# TMR1_v2.net
KiCad netlist of a schematic drawn in EAGLE
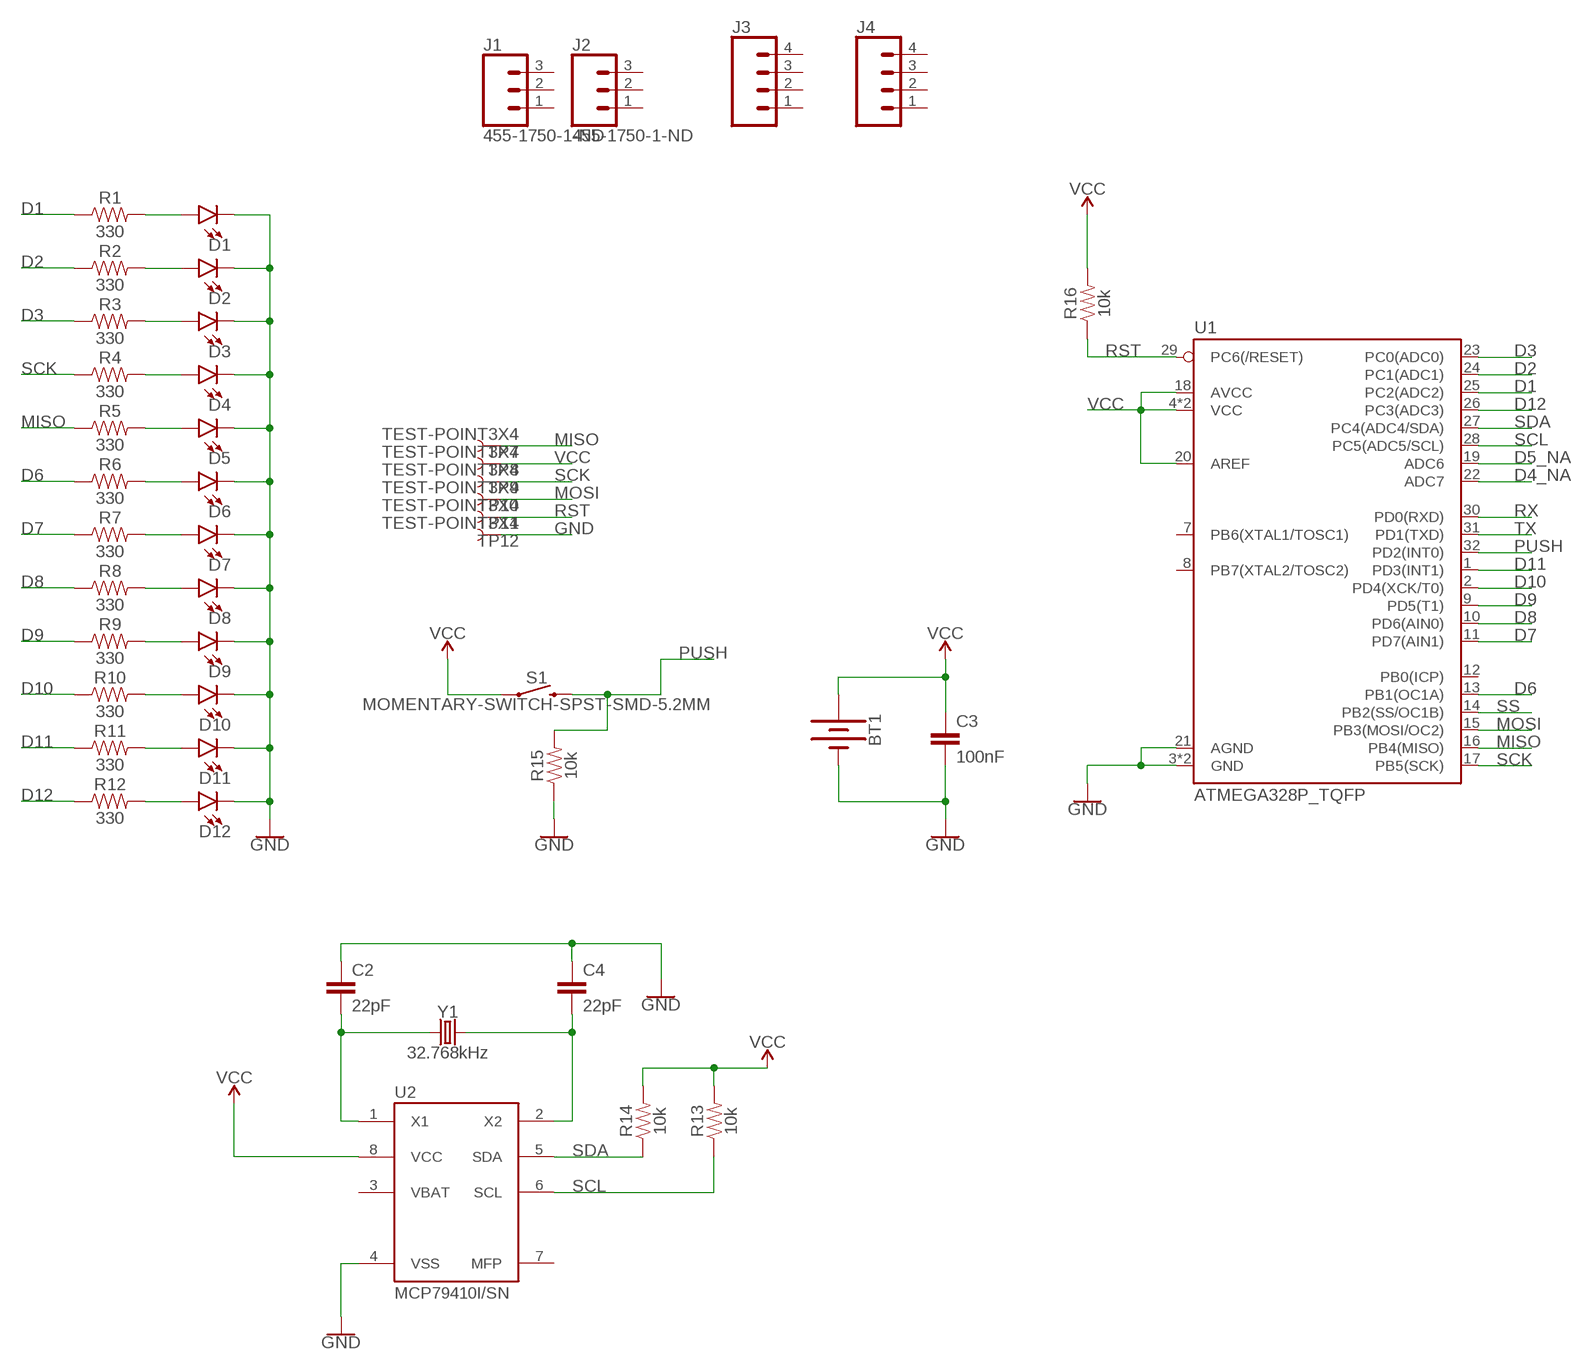
[diagram p0: schematic, sheet 1]

(export (version "E")
  (design (tool "Eeschema 10.0.6"))
  (components
    (comp (ref "BT1")
      (value "BATTERY-20MM_SMD_4LEGS")
      (footprint "eagle-import:BATTCON_20MM_4LEGS")
      (libsource (lib "eagle-import") (part "BATTERY-20MM_SMD_4LEGS"))
    )
    (comp (ref "C2")
      (value "22pF")
      (footprint "eagle-import:0603")
      (libsource (lib "eagle-import") (part "22PF-0603-50V-5%"))
    )
    (comp (ref "C3")
      (value "100nF")
      (footprint "eagle-import:0603")
      (libsource (lib "eagle-import") (part "22PF-0603-50V-5%"))
    )
    (comp (ref "C4")
      (value "22pF")
      (footprint "eagle-import:0603")
      (libsource (lib "eagle-import") (part "22PF-0603-50V-5%"))
    )
    (comp (ref "D1")
      (value "LED0603")
      (footprint "eagle-import:LED-0603")
      (libsource (lib "eagle-import") (part "LED0603"))
    )
    (comp (ref "D2")
      (value "LED0603")
      (footprint "eagle-import:LED-0603")
      (libsource (lib "eagle-import") (part "LED0603"))
    )
    (comp (ref "D3")
      (value "LED0603")
      (footprint "eagle-import:LED-0603")
      (libsource (lib "eagle-import") (part "LED0603"))
    )
    (comp (ref "D4")
      (value "LED0603")
      (footprint "eagle-import:LED-0603")
      (libsource (lib "eagle-import") (part "LED0603"))
    )
    (comp (ref "D5")
      (value "LED0603")
      (footprint "eagle-import:LED-0603")
      (libsource (lib "eagle-import") (part "LED0603"))
    )
    (comp (ref "D6")
      (value "LED0603")
      (footprint "eagle-import:LED-0603")
      (libsource (lib "eagle-import") (part "LED0603"))
    )
    (comp (ref "D7")
      (value "LED0603")
      (footprint "eagle-import:LED-0603")
      (libsource (lib "eagle-import") (part "LED0603"))
    )
    (comp (ref "D8")
      (value "LED0603")
      (footprint "eagle-import:LED-0603")
      (libsource (lib "eagle-import") (part "LED0603"))
    )
    (comp (ref "D9")
      (value "LED0603")
      (footprint "eagle-import:LED-0603")
      (libsource (lib "eagle-import") (part "LED0603"))
    )
    (comp (ref "D10")
      (value "LED0603")
      (footprint "eagle-import:LED-0603")
      (libsource (lib "eagle-import") (part "LED0603"))
    )
    (comp (ref "D11")
      (value "LED0603")
      (footprint "eagle-import:LED-0603")
      (libsource (lib "eagle-import") (part "LED0603"))
    )
    (comp (ref "D12")
      (value "LED0603")
      (footprint "eagle-import:LED-0603")
      (libsource (lib "eagle-import") (part "LED0603"))
    )
    (comp (ref "J1")
      (value "455-1750-1-ND")
      (footprint "eagle-import:1X03")
      (libsource (lib "eagle-import") (part "CONN_03"))
    )
    (comp (ref "J2")
      (value "455-1750-1-ND")
      (footprint "eagle-import:1X03")
      (libsource (lib "eagle-import") (part "CONN_03"))
    )
    (comp (ref "J3")
      (value "CONN_04")
      (footprint "eagle-import:1X04")
      (libsource (lib "eagle-import") (part "CONN_04"))
    )
    (comp (ref "J4")
      (value "CONN_04")
      (footprint "eagle-import:1X04")
      (libsource (lib "eagle-import") (part "CONN_04"))
    )
    (comp (ref "R1")
      (value "330")
      (footprint "eagle-import:0603")
      (libsource (lib "eagle-import") (part "330OHM-0603-1/10W-1%"))
    )
    (comp (ref "R2")
      (value "330")
      (footprint "eagle-import:0603")
      (libsource (lib "eagle-import") (part "330OHM-0603-1/10W-1%"))
    )
    (comp (ref "R3")
      (value "330")
      (footprint "eagle-import:0603")
      (libsource (lib "eagle-import") (part "330OHM-0603-1/10W-1%"))
    )
    (comp (ref "R4")
      (value "330")
      (footprint "eagle-import:0603")
      (libsource (lib "eagle-import") (part "330OHM-0603-1/10W-1%"))
    )
    (comp (ref "R5")
      (value "330")
      (footprint "eagle-import:0603")
      (libsource (lib "eagle-import") (part "330OHM-0603-1/10W-1%"))
    )
    (comp (ref "R6")
      (value "330")
      (footprint "eagle-import:0603")
      (libsource (lib "eagle-import") (part "330OHM-0603-1/10W-1%"))
    )
    (comp (ref "R7")
      (value "330")
      (footprint "eagle-import:0603")
      (libsource (lib "eagle-import") (part "330OHM-0603-1/10W-1%"))
    )
    (comp (ref "R8")
      (value "330")
      (footprint "eagle-import:0603")
      (libsource (lib "eagle-import") (part "330OHM-0603-1/10W-1%"))
    )
    (comp (ref "R9")
      (value "330")
      (footprint "eagle-import:0603")
      (libsource (lib "eagle-import") (part "330OHM-0603-1/10W-1%"))
    )
    (comp (ref "R10")
      (value "330")
      (footprint "eagle-import:0603")
      (libsource (lib "eagle-import") (part "330OHM-0603-1/10W-1%"))
    )
    (comp (ref "R11")
      (value "330")
      (footprint "eagle-import:0603")
      (libsource (lib "eagle-import") (part "330OHM-0603-1/10W-1%"))
    )
    (comp (ref "R12")
      (value "330")
      (footprint "eagle-import:0603")
      (libsource (lib "eagle-import") (part "330OHM-0603-1/10W-1%"))
    )
    (comp (ref "R13")
      (value "10k")
      (footprint "eagle-import:0603")
      (libsource (lib "eagle-import") (part "10KOHM-0603-1/10W-1%"))
    )
    (comp (ref "R14")
      (value "10k")
      (footprint "eagle-import:0603")
      (libsource (lib "eagle-import") (part "10KOHM-0603-1/10W-1%"))
    )
    (comp (ref "R15")
      (value "10k")
      (footprint "eagle-import:0603")
      (libsource (lib "eagle-import") (part "10KOHM-0603-1/10W-1%"))
    )
    (comp (ref "R16")
      (value "10k")
      (footprint "eagle-import:0603")
      (libsource (lib "eagle-import") (part "10KOHM-0603-1/10W-1%"))
    )
    (comp (ref "S1")
      (value "MOMENTARY-SWITCH-SPST-SMD-5.2MM")
      (footprint "eagle-import:TACTILE_SWITCH_SMD_5.2MM")
      (libsource (lib "eagle-import") (part "MOMENTARY-SWITCH-SPST-SMD-5.2MM"))
    )
    (comp (ref "TP7")
      (value "TEST-POINT3X4")
      (footprint "eagle-import:PAD.03X.04")
      (libsource (lib "eagle-import") (part "TEST-POINT3X4"))
    )
    (comp (ref "TP8")
      (value "TEST-POINT3X4")
      (footprint "eagle-import:PAD.03X.04")
      (libsource (lib "eagle-import") (part "TEST-POINT3X4"))
    )
    (comp (ref "TP9")
      (value "TEST-POINT3X4")
      (footprint "eagle-import:PAD.03X.04")
      (libsource (lib "eagle-import") (part "TEST-POINT3X4"))
    )
    (comp (ref "TP10")
      (value "TEST-POINT3X4")
      (footprint "eagle-import:PAD.03X.04")
      (libsource (lib "eagle-import") (part "TEST-POINT3X4"))
    )
    (comp (ref "TP11")
      (value "TEST-POINT3X4")
      (footprint "eagle-import:PAD.03X.04")
      (libsource (lib "eagle-import") (part "TEST-POINT3X4"))
    )
    (comp (ref "TP12")
      (value "TEST-POINT3X4")
      (footprint "eagle-import:PAD.03X.04")
      (libsource (lib "eagle-import") (part "TEST-POINT3X4"))
    )
    (comp (ref "U1")
      (value "ATMEGA328P_TQFP")
      (footprint "eagle-import:TQFP32-08")
      (libsource (lib "eagle-import") (part "ATMEGA328P_TQFP"))
    )
    (comp (ref "U2")
      (value "MCP79410I/SN")
      (footprint "eagle-import:SO8")
      (libsource (lib "eagle-import") (part "MCP7941?/SN0I"))
    )
    (comp (ref "Y1")
      (value "32.768kHz")
      (footprint "eagle-import:CRYSTAL-SMD-MC-146")
      (libsource (lib "eagle-import") (part "CRYSTAL-32.768KHZSMD-MC146"))
    )
  )
  (nets
    (net (code "1") (name "/D1") (class "Default")
      (node (ref "R1") (pin "1") (pinfunction "1_1") (pintype "passive"))
      (node (ref "U1") (pin "25") (pinfunction "PC2(ADC2)_25") (pintype "bidirectional"))
    )
    (net (code "2") (name "/D2") (class "Default")
      (node (ref "R2") (pin "1") (pinfunction "1_1") (pintype "passive"))
      (node (ref "U1") (pin "24") (pinfunction "PC1(ADC1)_24") (pintype "bidirectional"))
    )
    (net (code "3") (name "/D3") (class "Default")
      (node (ref "R3") (pin "1") (pinfunction "1_1") (pintype "passive"))
      (node (ref "U1") (pin "23") (pinfunction "PC0(ADC0)_23") (pintype "bidirectional"))
    )
    (net (code "4") (name "/D4_NA") (class "Default")
      (node (ref "U1") (pin "22") (pinfunction "ADC7_22") (pintype "bidirectional"))
    )
    (net (code "5") (name "/D5_NA") (class "Default")
      (node (ref "U1") (pin "19") (pinfunction "ADC6_19") (pintype "bidirectional"))
    )
    (net (code "6") (name "/D6") (class "Default")
      (node (ref "R6") (pin "1") (pinfunction "1_1") (pintype "passive"))
      (node (ref "U1") (pin "13") (pinfunction "PB1(OC1A)_13") (pintype "bidirectional"))
    )
    (net (code "7") (name "/D7") (class "Default")
      (node (ref "R7") (pin "1") (pinfunction "1_1") (pintype "passive"))
      (node (ref "U1") (pin "11") (pinfunction "PD7(AIN1)_11") (pintype "bidirectional"))
    )
    (net (code "8") (name "/D8") (class "Default")
      (node (ref "R8") (pin "1") (pinfunction "1_1") (pintype "passive"))
      (node (ref "U1") (pin "10") (pinfunction "PD6(AIN0)_10") (pintype "bidirectional"))
    )
    (net (code "9") (name "/D9") (class "Default")
      (node (ref "R9") (pin "1") (pinfunction "1_1") (pintype "passive"))
      (node (ref "U1") (pin "9") (pinfunction "PD5(T1)_9") (pintype "bidirectional"))
    )
    (net (code "10") (name "/D10") (class "Default")
      (node (ref "R10") (pin "1") (pinfunction "1_1") (pintype "passive"))
      (node (ref "U1") (pin "2") (pinfunction "PD4(XCK/T0)_2") (pintype "bidirectional"))
    )
    (net (code "11") (name "/D11") (class "Default")
      (node (ref "R11") (pin "1") (pinfunction "1_1") (pintype "passive"))
      (node (ref "U1") (pin "1") (pinfunction "PD3(INT1)_1") (pintype "bidirectional"))
    )
    (net (code "12") (name "/D12") (class "Default")
      (node (ref "R12") (pin "1") (pinfunction "1_1") (pintype "passive"))
      (node (ref "U1") (pin "26") (pinfunction "PC3(ADC3)_26") (pintype "bidirectional"))
    )
    (net (code "13") (name "/MISO") (class "Default")
      (node (ref "R5") (pin "1") (pinfunction "1_1") (pintype "passive"))
      (node (ref "TP7") (pin "P$1") (pinfunction "1_P$1") (pintype "bidirectional"))
      (node (ref "U1") (pin "16") (pinfunction "PB4(MISO)_16") (pintype "bidirectional"))
    )
    (net (code "14") (name "/MOSI") (class "Default")
      (node (ref "TP10") (pin "P$1") (pinfunction "1_P$1") (pintype "bidirectional"))
      (node (ref "U1") (pin "15") (pinfunction "PB3(MOSI/OC2)_15") (pintype "bidirectional"))
    )
    (net (code "15") (name "/PUSH") (class "Default")
      (node (ref "R15") (pin "2") (pinfunction "2_2") (pintype "passive"))
      (node (ref "S1") (pin "3") (pinfunction "2_3") (pintype "passive"))
      (node (ref "U1") (pin "32") (pinfunction "PD2(INT0)_32") (pintype "bidirectional"))
    )
    (net (code "16") (name "/RST") (class "Default")
      (node (ref "R16") (pin "1") (pinfunction "1_1") (pintype "passive"))
      (node (ref "TP11") (pin "P$1") (pinfunction "1_P$1") (pintype "bidirectional"))
      (node (ref "U1") (pin "29") (pinfunction "PC6(/RESET)_29") (pintype "bidirectional"))
    )
    (net (code "17") (name "/RX") (class "Default")
      (node (ref "U1") (pin "30") (pinfunction "PD0(RXD)_30") (pintype "bidirectional"))
    )
    (net (code "18") (name "/SCK") (class "Default")
      (node (ref "R4") (pin "1") (pinfunction "1_1") (pintype "passive"))
      (node (ref "TP9") (pin "P$1") (pinfunction "1_P$1") (pintype "bidirectional"))
      (node (ref "U1") (pin "17") (pinfunction "PB5(SCK)_17") (pintype "bidirectional"))
    )
    (net (code "19") (name "/SCL") (class "Default")
      (node (ref "R13") (pin "1") (pinfunction "1_1") (pintype "passive"))
      (node (ref "U1") (pin "28") (pinfunction "PC5(ADC5/SCL)_28") (pintype "bidirectional"))
      (node (ref "U2") (pin "6") (pinfunction "SCL_6") (pintype "input"))
    )
    (net (code "20") (name "/SDA") (class "Default")
      (node (ref "R14") (pin "1") (pinfunction "1_1") (pintype "passive"))
      (node (ref "U1") (pin "27") (pinfunction "PC4(ADC4/SDA)_27") (pintype "bidirectional"))
      (node (ref "U2") (pin "5") (pinfunction "SDA_5") (pintype "open_collector"))
    )
    (net (code "21") (name "/SS") (class "Default")
      (node (ref "U1") (pin "14") (pinfunction "PB2(SS/OC1B)_14") (pintype "bidirectional"))
    )
    (net (code "22") (name "/TX") (class "Default")
      (node (ref "U1") (pin "31") (pinfunction "PD1(TXD)_31") (pintype "bidirectional"))
    )
    (net (code "23") (name "/VBAT") (class "Default")
      (node (ref "U2") (pin "3") (pinfunction "VBAT_3") (pintype "power_in"))
    )
    (net (code "24") (name "GND") (class "Default")
      (node (ref "BT1") (pin "NEGATIVE") (pinfunction "-_NEGATIVE") (pintype "power_in"))
      (node (ref "C2") (pin "1") (pinfunction "1_1") (pintype "passive"))
      (node (ref "C3") (pin "2") (pinfunction "2_2") (pintype "passive"))
      (node (ref "C4") (pin "1") (pinfunction "1_1") (pintype "passive"))
      (node (ref "D1") (pin "C") (pinfunction "C_C") (pintype "passive"))
      (node (ref "D10") (pin "C") (pinfunction "C_C") (pintype "passive"))
      (node (ref "D11") (pin "C") (pinfunction "C_C") (pintype "passive"))
      (node (ref "D12") (pin "C") (pinfunction "C_C") (pintype "passive"))
      (node (ref "D2") (pin "C") (pinfunction "C_C") (pintype "passive"))
      (node (ref "D3") (pin "C") (pinfunction "C_C") (pintype "passive"))
      (node (ref "D4") (pin "C") (pinfunction "C_C") (pintype "passive"))
      (node (ref "D5") (pin "C") (pinfunction "C_C") (pintype "passive"))
      (node (ref "D6") (pin "C") (pinfunction "C_C") (pintype "passive"))
      (node (ref "D7") (pin "C") (pinfunction "C_C") (pintype "passive"))
      (node (ref "D8") (pin "C") (pinfunction "C_C") (pintype "passive"))
      (node (ref "D9") (pin "C") (pinfunction "C_C") (pintype "passive"))
      (node (ref "R15") (pin "1") (pinfunction "1_1") (pintype "passive"))
      (node (ref "TP12") (pin "P$1") (pinfunction "1_P$1") (pintype "bidirectional"))
      (node (ref "U1") (pin "21") (pinfunction "AGND_21") (pintype "bidirectional"))
      (node (ref "U1") (pin "3") (pinfunction "GND_3") (pintype "bidirectional"))
      (node (ref "U1") (pin "5") (pinfunction "GND_5") (pintype "bidirectional"))
      (node (ref "U2") (pin "4") (pinfunction "VSS_4") (pintype "power_in"))
    )
    (net (code "25") (name "Net-(D1-PadA)") (class "Default")
      (node (ref "D1") (pin "A") (pinfunction "A_A") (pintype "passive"))
      (node (ref "R1") (pin "2") (pinfunction "2_2") (pintype "passive"))
    )
    (net (code "26") (name "Net-(D2-PadA)") (class "Default")
      (node (ref "D2") (pin "A") (pinfunction "A_A") (pintype "passive"))
      (node (ref "R2") (pin "2") (pinfunction "2_2") (pintype "passive"))
    )
    (net (code "27") (name "Net-(D3-PadA)") (class "Default")
      (node (ref "D3") (pin "A") (pinfunction "A_A") (pintype "passive"))
      (node (ref "R3") (pin "2") (pinfunction "2_2") (pintype "passive"))
    )
    (net (code "28") (name "Net-(D4-PadA)") (class "Default")
      (node (ref "D4") (pin "A") (pinfunction "A_A") (pintype "passive"))
      (node (ref "R4") (pin "2") (pinfunction "2_2") (pintype "passive"))
    )
    (net (code "29") (name "Net-(D5-PadA)") (class "Default")
      (node (ref "D5") (pin "A") (pinfunction "A_A") (pintype "passive"))
      (node (ref "R5") (pin "2") (pinfunction "2_2") (pintype "passive"))
    )
    (net (code "30") (name "Net-(D6-PadA)") (class "Default")
      (node (ref "D6") (pin "A") (pinfunction "A_A") (pintype "passive"))
      (node (ref "R6") (pin "2") (pinfunction "2_2") (pintype "passive"))
    )
    (net (code "31") (name "Net-(D7-PadA)") (class "Default")
      (node (ref "D7") (pin "A") (pinfunction "A_A") (pintype "passive"))
      (node (ref "R7") (pin "2") (pinfunction "2_2") (pintype "passive"))
    )
    (net (code "32") (name "Net-(D8-PadA)") (class "Default")
      (node (ref "D8") (pin "A") (pinfunction "A_A") (pintype "passive"))
      (node (ref "R8") (pin "2") (pinfunction "2_2") (pintype "passive"))
    )
    (net (code "33") (name "Net-(D9-PadA)") (class "Default")
      (node (ref "D9") (pin "A") (pinfunction "A_A") (pintype "passive"))
      (node (ref "R9") (pin "2") (pinfunction "2_2") (pintype "passive"))
    )
    (net (code "34") (name "Net-(D10-PadA)") (class "Default")
      (node (ref "D10") (pin "A") (pinfunction "A_A") (pintype "passive"))
      (node (ref "R10") (pin "2") (pinfunction "2_2") (pintype "passive"))
    )
    (net (code "35") (name "Net-(D11-PadA)") (class "Default")
      (node (ref "D11") (pin "A") (pinfunction "A_A") (pintype "passive"))
      (node (ref "R11") (pin "2") (pinfunction "2_2") (pintype "passive"))
    )
    (net (code "36") (name "Net-(D12-PadA)") (class "Default")
      (node (ref "D12") (pin "A") (pinfunction "A_A") (pintype "passive"))
      (node (ref "R12") (pin "2") (pinfunction "2_2") (pintype "passive"))
    )
    (net (code "37") (name "Net-(U2-X1)") (class "Default")
      (node (ref "C2") (pin "2") (pinfunction "2_2") (pintype "passive"))
      (node (ref "U2") (pin "1") (pinfunction "X1_1") (pintype "input"))
      (node (ref "Y1") (pin "P$2") (pinfunction "1_P$2") (pintype "passive"))
    )
    (net (code "38") (name "Net-(U2-X2)") (class "Default")
      (node (ref "C4") (pin "2") (pinfunction "2_2") (pintype "passive"))
      (node (ref "U2") (pin "2") (pinfunction "X2_2") (pintype "output"))
      (node (ref "Y1") (pin "P$1") (pinfunction "2_P$1") (pintype "passive"))
    )
    (net (code "39") (name "VCC") (class "Default")
      (node (ref "BT1") (pin "POSITIVE@1") (pinfunction "+_POSITIVE@1") (pintype "power_in"))
      (node (ref "BT1") (pin "POSITIVE@2") (pinfunction "+_POSITIVE@2") (pintype "power_in"))
      (node (ref "BT1") (pin "POSITIVE@3") (pinfunction "+_POSITIVE@3") (pintype "power_in"))
      (node (ref "BT1") (pin "POSITIVE@4") (pinfunction "+_POSITIVE@4") (pintype "power_in"))
      (node (ref "C3") (pin "1") (pinfunction "1_1") (pintype "passive"))
      (node (ref "R13") (pin "2") (pinfunction "2_2") (pintype "passive"))
      (node (ref "R14") (pin "2") (pinfunction "2_2") (pintype "passive"))
      (node (ref "R16") (pin "2") (pinfunction "2_2") (pintype "passive"))
      (node (ref "S1") (pin "1") (pinfunction "1_1") (pintype "passive"))
      (node (ref "TP8") (pin "P$1") (pinfunction "1_P$1") (pintype "bidirectional"))
      (node (ref "U1") (pin "18") (pinfunction "AVCC_18") (pintype "bidirectional"))
      (node (ref "U1") (pin "20") (pinfunction "AREF_20") (pintype "bidirectional"))
      (node (ref "U1") (pin "4") (pinfunction "VCC_4") (pintype "bidirectional"))
      (node (ref "U1") (pin "6") (pinfunction "VCC_6") (pintype "bidirectional"))
      (node (ref "U2") (pin "8") (pinfunction "VCC_8") (pintype "power_in"))
    )
    (net (code "40") (name "unconnected-(J1-Pad1)") (class "Default")
      (node (ref "J1") (pin "1") (pinfunction "1_1") (pintype "passive"))
    )
    (net (code "41") (name "unconnected-(J1-Pad2)") (class "Default")
      (node (ref "J1") (pin "2") (pinfunction "2_2") (pintype "passive"))
    )
    (net (code "42") (name "unconnected-(J1-Pad3)") (class "Default")
      (node (ref "J1") (pin "3") (pinfunction "3_3") (pintype "passive"))
    )
    (net (code "43") (name "unconnected-(J2-Pad1)") (class "Default")
      (node (ref "J2") (pin "1") (pinfunction "1_1") (pintype "passive"))
    )
    (net (code "44") (name "unconnected-(J2-Pad2)") (class "Default")
      (node (ref "J2") (pin "2") (pinfunction "2_2") (pintype "passive"))
    )
    (net (code "45") (name "unconnected-(J2-Pad3)") (class "Default")
      (node (ref "J2") (pin "3") (pinfunction "3_3") (pintype "passive"))
    )
    (net (code "46") (name "unconnected-(J3-Pad1)") (class "Default")
      (node (ref "J3") (pin "1") (pinfunction "1_1") (pintype "passive"))
    )
    (net (code "47") (name "unconnected-(J3-Pad2)") (class "Default")
      (node (ref "J3") (pin "2") (pinfunction "2_2") (pintype "passive"))
    )
    (net (code "48") (name "unconnected-(J3-Pad3)") (class "Default")
      (node (ref "J3") (pin "3") (pinfunction "3_3") (pintype "passive"))
    )
    (net (code "49") (name "unconnected-(J3-Pad4)") (class "Default")
      (node (ref "J3") (pin "4") (pinfunction "4_4") (pintype "passive"))
    )
    (net (code "50") (name "unconnected-(J4-Pad1)") (class "Default")
      (node (ref "J4") (pin "1") (pinfunction "1_1") (pintype "passive"))
    )
    (net (code "51") (name "unconnected-(J4-Pad2)") (class "Default")
      (node (ref "J4") (pin "2") (pinfunction "2_2") (pintype "passive"))
    )
    (net (code "52") (name "unconnected-(J4-Pad3)") (class "Default")
      (node (ref "J4") (pin "3") (pinfunction "3_3") (pintype "passive"))
    )
    (net (code "53") (name "unconnected-(J4-Pad4)") (class "Default")
      (node (ref "J4") (pin "4") (pinfunction "4_4") (pintype "passive"))
    )
    (net (code "54") (name "unconnected-(U1-PB0(ICP)-Pad12)") (class "Default")
      (node (ref "U1") (pin "12") (pinfunction "PB0(ICP)_12") (pintype "bidirectional"))
    )
    (net (code "55") (name "unconnected-(U1-PB6(XTAL1{slash}TOSC1)-Pad7)") (class "Default")
      (node (ref "U1") (pin "7") (pinfunction "PB6(XTAL1/TOSC1)_7") (pintype "bidirectional"))
    )
    (net (code "56") (name "unconnected-(U1-PB7(XTAL2{slash}TOSC2)-Pad8)") (class "Default")
      (node (ref "U1") (pin "8") (pinfunction "PB7(XTAL2/TOSC2)_8") (pintype "bidirectional"))
    )
    (net (code "57") (name "unconnected-(U2-MFP-Pad7)") (class "Default")
      (node (ref "U2") (pin "7") (pinfunction "MFP_7") (pintype "open_collector"))
    )
  )
)
